# Power.net
KiCad netlist of a schematic drawn in Altium Designer
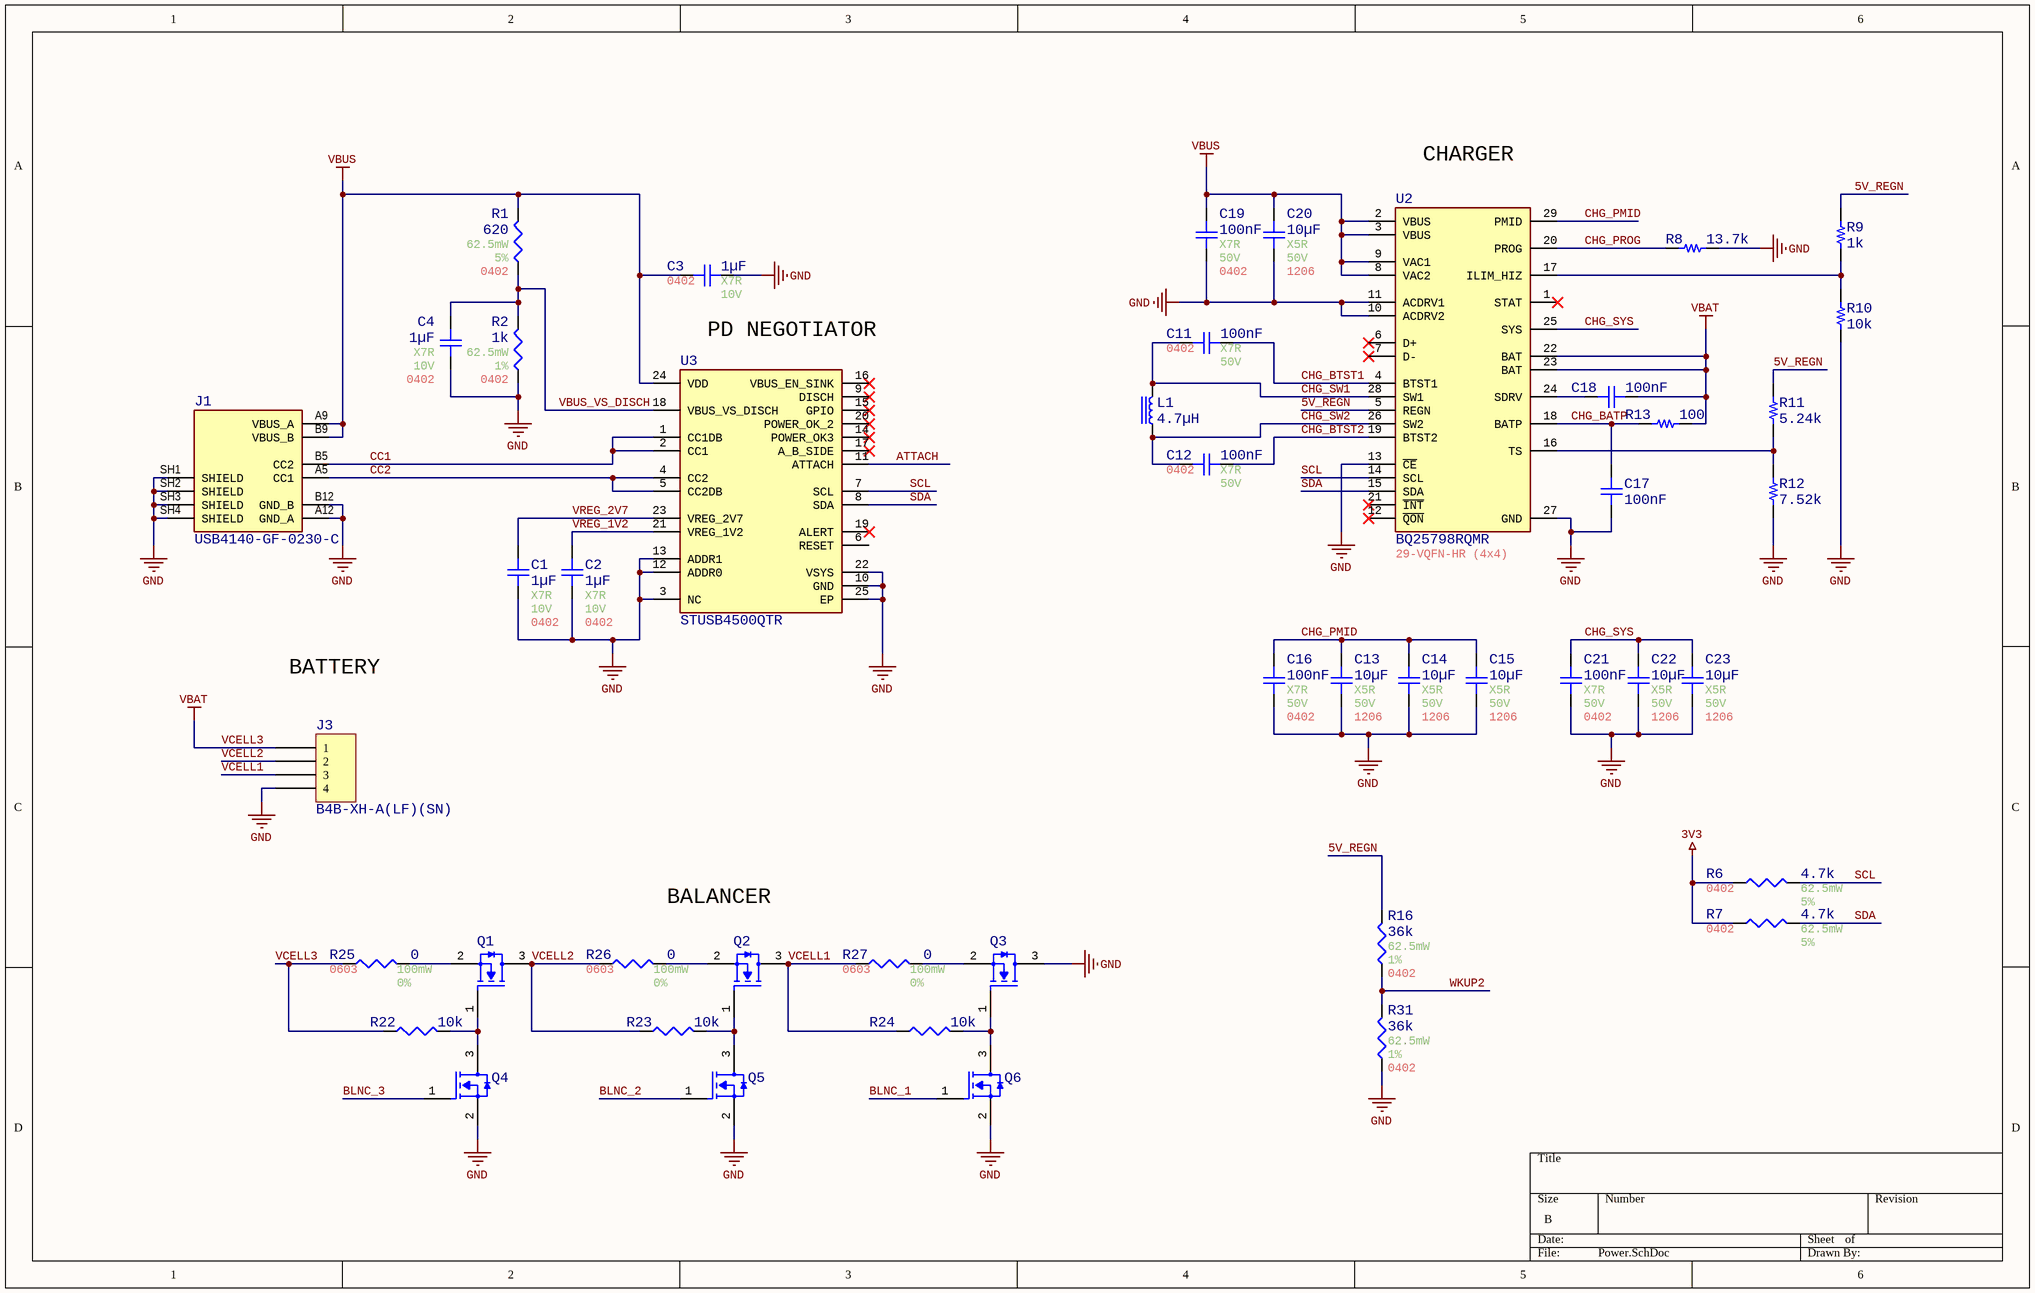
[diagram p0: Power.SchDoc]

(export (version "E")
  (design (tool "Eeschema 10.0.6"))
  (components
    (comp (ref "C1")
      (value "1µF")
      (footprint "Generic 0402 capacitor")
      (description "Cap Cer 1UF 20V X7T 0402")
      (fields
        (field (name "TEMPERATURE COEFFICIENT") "X7R")
        (field (name "VOLTAGE RATING") "10V")
        (field (name "CASE/PACKAGE") "0402")
        (field (name "TOLERANCE") "20%")
        (field (name "Comment") "MAASL105CD7105MFCA01")
      )
      (libsource (lib "Raise Robotics") (part "Unpolarized Capacitor"))
    )
    (comp (ref "C2")
      (value "1µF")
      (footprint "Generic 0402 capacitor")
      (description "Cap Cer 1UF 20V X7T 0402")
      (fields
        (field (name "TEMPERATURE COEFFICIENT") "X7R")
        (field (name "VOLTAGE RATING") "10V")
        (field (name "CASE/PACKAGE") "0402")
        (field (name "TOLERANCE") "20%")
        (field (name "Comment") "MAASL105CD7105MFCA01")
      )
      (libsource (lib "Raise Robotics") (part "Unpolarized Capacitor"))
    )
    (comp (ref "C3")
      (value "1µF")
      (footprint "Generic 0402 capacitor")
      (description "Cap Cer 1UF 20V X7T 0402")
      (fields
        (field (name "TEMPERATURE COEFFICIENT") "X7R")
        (field (name "VOLTAGE RATING") "10V")
        (field (name "CASE/PACKAGE") "0402")
        (field (name "TOLERANCE") "20%")
        (field (name "Comment") "MAASL105CD7105MFCA01")
      )
      (libsource (lib "Raise Robotics") (part "Unpolarized Capacitor"))
    )
    (comp (ref "C4")
      (value "1µF")
      (footprint "Generic 0402 capacitor")
      (description "Cap Cer 1UF 20V X7T 0402")
      (fields
        (field (name "TEMPERATURE COEFFICIENT") "X7R")
        (field (name "VOLTAGE RATING") "10V")
        (field (name "CASE/PACKAGE") "0402")
        (field (name "TOLERANCE") "20%")
        (field (name "Comment") "MAASL105CD7105MFCA01")
      )
      (libsource (lib "Raise Robotics") (part "Unpolarized Capacitor"))
    )
    (comp (ref "C11")
      (value "100nF")
      (footprint "Generic 0402 capacitor")
      (fields
        (field (name "TEMPERATURE COEFFICIENT") "X7R")
        (field (name "VOLTAGE RATING") "50V")
        (field (name "CASE/PACKAGE") "0402")
        (field (name "TOLERANCE") "10%")
        (field (name "Comment") "GRT155R71H104KE01D")
      )
      (libsource (lib "Raise Robotics") (part "Unpolarized Capacitor"))
    )
    (comp (ref "C12")
      (value "100nF")
      (footprint "Generic 0402 capacitor")
      (fields
        (field (name "TEMPERATURE COEFFICIENT") "X7R")
        (field (name "VOLTAGE RATING") "50V")
        (field (name "CASE/PACKAGE") "0402")
        (field (name "TOLERANCE") "10%")
        (field (name "Comment") "GRT155R71H104KE01D")
      )
      (libsource (lib "Raise Robotics") (part "Unpolarized Capacitor"))
    )
    (comp (ref "C13")
      (value "10µF")
      (footprint "Generic 1206 Capacitor")
      (fields
        (field (name "TEMPERATURE COEFFICIENT") "X5R")
        (field (name "VOLTAGE RATING") "50V")
        (field (name "CASE/PACKAGE") "1206")
        (field (name "TOLERANCE") "20%")
        (field (name "Comment") "CL31A106MBHNNNE")
      )
      (libsource (lib "Raise Robotics") (part "Unpolarized Capacitor"))
    )
    (comp (ref "C14")
      (value "10µF")
      (footprint "Generic 1206 Capacitor")
      (fields
        (field (name "TEMPERATURE COEFFICIENT") "X5R")
        (field (name "VOLTAGE RATING") "50V")
        (field (name "CASE/PACKAGE") "1206")
        (field (name "TOLERANCE") "20%")
        (field (name "Comment") "CL31A106MBHNNNE")
      )
      (libsource (lib "Raise Robotics") (part "Unpolarized Capacitor"))
    )
    (comp (ref "C15")
      (value "10µF")
      (footprint "Generic 1206 Capacitor")
      (fields
        (field (name "TEMPERATURE COEFFICIENT") "X5R")
        (field (name "VOLTAGE RATING") "50V")
        (field (name "CASE/PACKAGE") "1206")
        (field (name "TOLERANCE") "20%")
        (field (name "Comment") "CL31A106MBHNNNE")
      )
      (libsource (lib "Raise Robotics") (part "Unpolarized Capacitor"))
    )
    (comp (ref "C16")
      (value "100nF")
      (footprint "Generic 0402 capacitor")
      (fields
        (field (name "TEMPERATURE COEFFICIENT") "X7R")
        (field (name "VOLTAGE RATING") "50V")
        (field (name "CASE/PACKAGE") "0402")
        (field (name "TOLERANCE") "10%")
        (field (name "Comment") "GRT155R71H104KE01D")
      )
      (libsource (lib "Raise Robotics") (part "Unpolarized Capacitor"))
    )
    (comp (ref "C17")
      (value "100nF")
      (footprint "Generic 0402 capacitor")
      (fields (field (name "TOLERANCE") "10%") (field (name "Comment") "GRT155R71H104KE01D"))
      (libsource (lib "Raise Robotics") (part "Unpolarized Capacitor"))
    )
    (comp (ref "C18")
      (value "100nF")
      (footprint "Generic 0402 capacitor")
      (fields (field (name "TOLERANCE") "10%") (field (name "Comment") "GRT155R71H104KE01D"))
      (libsource (lib "Raise Robotics") (part "Unpolarized Capacitor"))
    )
    (comp (ref "C19")
      (value "100nF")
      (footprint "Generic 0402 capacitor")
      (fields
        (field (name "TEMPERATURE COEFFICIENT") "X7R")
        (field (name "VOLTAGE RATING") "50V")
        (field (name "CASE/PACKAGE") "0402")
        (field (name "TOLERANCE") "10%")
        (field (name "Comment") "GRT155R71H104KE01D")
      )
      (libsource (lib "Raise Robotics") (part "Unpolarized Capacitor"))
    )
    (comp (ref "C20")
      (value "10µF")
      (footprint "Generic 1206 Capacitor")
      (fields
        (field (name "TEMPERATURE COEFFICIENT") "X5R")
        (field (name "VOLTAGE RATING") "50V")
        (field (name "CASE/PACKAGE") "1206")
        (field (name "TOLERANCE") "20%")
        (field (name "Comment") "CL31A106MBHNNNE")
      )
      (libsource (lib "Raise Robotics") (part "Unpolarized Capacitor"))
    )
    (comp (ref "C21")
      (value "100nF")
      (footprint "Generic 0402 capacitor")
      (fields
        (field (name "TEMPERATURE COEFFICIENT") "X7R")
        (field (name "VOLTAGE RATING") "50V")
        (field (name "CASE/PACKAGE") "0402")
        (field (name "TOLERANCE") "10%")
        (field (name "Comment") "GRT155R71H104KE01D")
      )
      (libsource (lib "Raise Robotics") (part "Unpolarized Capacitor"))
    )
    (comp (ref "C22")
      (value "10µF")
      (footprint "Generic 1206 Capacitor")
      (fields
        (field (name "TEMPERATURE COEFFICIENT") "X5R")
        (field (name "VOLTAGE RATING") "50V")
        (field (name "CASE/PACKAGE") "1206")
        (field (name "TOLERANCE") "20%")
        (field (name "Comment") "CL31A106MBHNNNE")
      )
      (libsource (lib "Raise Robotics") (part "Unpolarized Capacitor"))
    )
    (comp (ref "C23")
      (value "10µF")
      (footprint "Generic 1206 Capacitor")
      (fields
        (field (name "TEMPERATURE COEFFICIENT") "X5R")
        (field (name "VOLTAGE RATING") "50V")
        (field (name "CASE/PACKAGE") "1206")
        (field (name "TOLERANCE") "20%")
        (field (name "Comment") "CL31A106MBHNNNE")
      )
      (libsource (lib "Raise Robotics") (part "Unpolarized Capacitor"))
    )
    (comp (ref "J1")
      (value "USB4140-GF-0230-C")
      (footprint "USB4140-GF-0230-C")
      (description "USB Connector, 6 Contact(s), Female, Straight, Surface Mount Terminal, Locking, Receptacle")
      (fields (field (name "MANUFACTURER") "Molex"))
      (libsource (lib "Raise Robotics") (part "USB4140-GF-0230-C"))
    )
    (comp (ref "J3")
      (value "B4B-XH-A(LF)(SN)")
      (footprint "JST XH B4B-XH-A")
      (description "CONN HEADER VERT 4POS 2.5MM")
      (fields (field (name "MANUFACTURER") "JST Sales America Inc."))
      (libsource (lib "Celestial Altium Library - altium_library") (part "4 Pin"))
    )
    (comp (ref "L1")
      (value "4.7µH")
      (footprint "IND 1008_2520")
      (description "FIXED IND 4.7UH 1A 110 MOHM SMD")
      (fields (field (name "PART NUMBER") "MLP2520S4R7ST0S1") (field (name "MANUFACTURER") "TDK Corporation"))
      (libsource (lib "Celestial Altium Library - altium_library") (part "Inductor"))
    )
    (comp (ref "Q1")
      (value "DMN61D9UWQ-7")
      (footprint "DMN61D9UWQ-7")
      (description "Small Signal Field-Effect Transistor")
      (libsource (lib "Raise Robotics") (part "n-FET 3 pin SOT"))
    )
    (comp (ref "Q2")
      (value "DMN61D9UWQ-7")
      (footprint "DMN61D9UWQ-7")
      (description "Small Signal Field-Effect Transistor")
      (libsource (lib "Raise Robotics") (part "n-FET 3 pin SOT"))
    )
    (comp (ref "Q3")
      (value "DMN61D9UWQ-7")
      (footprint "DMN61D9UWQ-7")
      (description "Small Signal Field-Effect Transistor")
      (libsource (lib "Raise Robotics") (part "n-FET 3 pin SOT"))
    )
    (comp (ref "Q4")
      (value "DMN61D9UWQ-7")
      (footprint "DMN61D9UWQ-7")
      (description "Small Signal Field-Effect Transistor")
      (libsource (lib "Raise Robotics") (part "n-FET 3 pin SOT"))
    )
    (comp (ref "Q5")
      (value "DMN61D9UWQ-7")
      (footprint "DMN61D9UWQ-7")
      (description "Small Signal Field-Effect Transistor")
      (libsource (lib "Raise Robotics") (part "n-FET 3 pin SOT"))
    )
    (comp (ref "Q6")
      (value "DMN61D9UWQ-7")
      (footprint "DMN61D9UWQ-7")
      (description "Small Signal Field-Effect Transistor")
      (libsource (lib "Raise Robotics") (part "n-FET 3 pin SOT"))
    )
    (comp (ref "R1")
      (value "620")
      (footprint "Generic 0402 Resistor")
      (fields
        (field (name "POWER") "62.5mW")
        (field (name "TOLERANCE") "5%")
        (field (name "CASE/PACKAGE") "0402")
        (field (name "Comment") "RC0402JR-07620RL")
      )
      (libsource (lib "Raise Robotics") (part "Resistor"))
    )
    (comp (ref "R2")
      (value "1k")
      (footprint "Generic 0402 Resistor")
      (fields
        (field (name "POWER") "62.5mW")
        (field (name "TOLERANCE") "1%")
        (field (name "CASE/PACKAGE") "0402")
        (field (name "MANUFACTURER PART NUMBER") "Blank")
        (field (name "Comment") "WR04X1001FTL")
      )
      (libsource (lib "Raise Robotics") (part "Resistor"))
    )
    (comp (ref "R6")
      (value "4.7k")
      (footprint "Generic 0402 Resistor")
      (fields
        (field (name "POWER") "62.5mW")
        (field (name "TOLERANCE") "5%")
        (field (name "CASE/PACKAGE") "0402")
        (field (name "MANUFACTURER PART NUMBER") "Blank")
        (field (name "Comment") "WR04X472JTL")
      )
      (libsource (lib "Raise Robotics") (part "Resistor"))
    )
    (comp (ref "R7")
      (value "4.7k")
      (footprint "Generic 0402 Resistor")
      (fields
        (field (name "POWER") "62.5mW")
        (field (name "TOLERANCE") "5%")
        (field (name "CASE/PACKAGE") "0402")
        (field (name "MANUFACTURER PART NUMBER") "Blank")
        (field (name "Comment") "WR04X472JTL")
      )
      (libsource (lib "Raise Robotics") (part "Resistor"))
    )
    (comp (ref "R8")
      (value "13.7k")
      (footprint "RES_0402")
      (description "RES 0402")
      (libsource (lib "IC") (part "RES_0402"))
    )
    (comp (ref "R9")
      (value "1k")
      (footprint "RES_0402")
      (description "RES 0402")
      (libsource (lib "IC") (part "RES_0402"))
    )
    (comp (ref "R10")
      (value "10k")
      (footprint "RES_0402")
      (description "RES 0402")
      (libsource (lib "IC") (part "RES_0402"))
    )
    (comp (ref "R11")
      (value "5.24k")
      (footprint "RES_0402")
      (description "RES 0402")
      (libsource (lib "IC") (part "RES_0402"))
    )
    (comp (ref "R12")
      (value "7.52k")
      (footprint "RES_0402")
      (description "RES 0402")
      (libsource (lib "IC") (part "RES_0402"))
    )
    (comp (ref "R13")
      (value "100")
      (footprint "RES_0402")
      (description "RES 0402")
      (libsource (lib "IC") (part "RES_0402"))
    )
    (comp (ref "R16")
      (value "36k")
      (footprint "Generic 0402 Resistor")
      (fields
        (field (name "POWER") "62.5mW")
        (field (name "TOLERANCE") "1%")
        (field (name "CASE/PACKAGE") "0402")
        (field (name "Comment") "AC0402FR-0736KL")
      )
      (libsource (lib "Raise Robotics") (part "Resistor"))
    )
    (comp (ref "R22")
      (value "10k")
      (footprint "Generic 0402 Resistor")
      (fields
        (field (name "POWER") "62.5mW")
        (field (name "TOLERANCE") "5%")
        (field (name "MANUFACTURER PART NUMBER") "Blank")
      )
      (libsource (lib "Raise Robotics") (part "Resistor"))
    )
    (comp (ref "R23")
      (value "10k")
      (footprint "Generic 0402 Resistor")
      (fields
        (field (name "POWER") "62.5mW")
        (field (name "TOLERANCE") "5%")
        (field (name "MANUFACTURER PART NUMBER") "Blank")
      )
      (libsource (lib "Raise Robotics") (part "Resistor"))
    )
    (comp (ref "R24")
      (value "10k")
      (footprint "Generic 0402 Resistor")
      (fields
        (field (name "POWER") "62.5mW")
        (field (name "TOLERANCE") "5%")
        (field (name "MANUFACTURER PART NUMBER") "Blank")
      )
      (libsource (lib "Raise Robotics") (part "Resistor"))
    )
    (comp (ref "R25")
      (value "0")
      (footprint "Generic 0603 Resistor")
      (description "Fixed Resistor, Metal Glaze/thick Film, 0.1W, 0ohm, Surface Mount, 0603")
      (fields
        (field (name "POWER") "100mW")
        (field (name "TOLERANCE") "0%")
        (field (name "CASE/PACKAGE") "0603")
        (field (name "MANUFACTURER PART NUMBER") "Blank")
        (field (name "Comment") "WR06X000PTL")
      )
      (libsource (lib "Raise Robotics") (part "Resistor"))
    )
    (comp (ref "R26")
      (value "0")
      (footprint "Generic 0603 Resistor")
      (description "Fixed Resistor, Metal Glaze/thick Film, 0.1W, 0ohm, Surface Mount, 0603")
      (fields
        (field (name "POWER") "100mW")
        (field (name "TOLERANCE") "0%")
        (field (name "CASE/PACKAGE") "0603")
        (field (name "MANUFACTURER PART NUMBER") "Blank")
        (field (name "Comment") "WR06X000PTL")
      )
      (libsource (lib "Raise Robotics") (part "Resistor"))
    )
    (comp (ref "R27")
      (value "0")
      (footprint "Generic 0603 Resistor")
      (description "Fixed Resistor, Metal Glaze/thick Film, 0.1W, 0ohm, Surface Mount, 0603")
      (fields
        (field (name "POWER") "100mW")
        (field (name "TOLERANCE") "0%")
        (field (name "CASE/PACKAGE") "0603")
        (field (name "MANUFACTURER PART NUMBER") "Blank")
        (field (name "Comment") "WR06X000PTL")
      )
      (libsource (lib "Raise Robotics") (part "Resistor"))
    )
    (comp (ref "R31")
      (value "36k")
      (footprint "Generic 0402 Resistor")
      (fields
        (field (name "POWER") "62.5mW")
        (field (name "TOLERANCE") "1%")
        (field (name "CASE/PACKAGE") "0402")
        (field (name "Comment") "AC0402FR-0736KL")
      )
      (libsource (lib "Raise Robotics") (part "Resistor"))
    )
    (comp (ref "U2")
      (value "BQ25798RQMR")
      (footprint "29-VQFN-HR (4x4)")
      (fields (field (name "CASE/PACKAGE") "29-VQFN-HR (4x4)"))
      (libsource (lib "Raise Robotics") (part "BQ25798"))
    )
    (comp (ref "U3")
      (value "STUSB4500QTR")
      (footprint "FP-QFN-24-EP_4x4-MFG")
      (description "Super Speed USB Controller USB 1.2/USB 2.0 5V/9V/12V/15V/18V T/R 24-Pin QFN EP")
      (libsource (lib "Raise Robotics") (part "STUSB4500QTR"))
    )
  )
  (nets
    (net (code "1") (name "/5V_REGN") (class "Default")
      (node (ref "R11") (pin "1") (pinfunction "1_1") (pintype "passive"))
      (node (ref "R16") (pin "2") (pinfunction "2_2") (pintype "passive"))
      (node (ref "R9") (pin "1") (pinfunction "1_1") (pintype "passive"))
      (node (ref "U2") (pin "5") (pinfunction "REGN_5") (pintype "passive"))
    )
    (net (code "2") (name "/ATTACH") (class "Default")
      (node (ref "U3") (pin "11") (pinfunction "ATTACH_11") (pintype "passive"))
    )
    (net (code "3") (name "/BLNC_1") (class "Default")
      (node (ref "Q6") (pin "1") (pinfunction "GATE_1") (pintype "passive"))
    )
    (net (code "4") (name "/BLNC_2") (class "Default")
      (node (ref "Q5") (pin "1") (pinfunction "GATE_1") (pintype "passive"))
    )
    (net (code "5") (name "/BLNC_3") (class "Default")
      (node (ref "Q4") (pin "1") (pinfunction "GATE_1") (pintype "passive"))
    )
    (net (code "6") (name "/CC1") (class "Default")
      (node (ref "J1") (pin "B5") (pinfunction "CC2_B5") (pintype "passive"))
      (node (ref "U3") (pin "1") (pinfunction "CC1DB_1") (pintype "passive"))
      (node (ref "U3") (pin "2") (pinfunction "CC1_2") (pintype "passive"))
    )
    (net (code "7") (name "/CC2") (class "Default")
      (node (ref "J1") (pin "A5") (pinfunction "CC1_A5") (pintype "passive"))
      (node (ref "U3") (pin "4") (pinfunction "CC2_4") (pintype "passive"))
      (node (ref "U3") (pin "5") (pinfunction "CC2DB_5") (pintype "passive"))
    )
    (net (code "8") (name "/CHG_BATP") (class "Default")
      (node (ref "C17") (pin "1") (pinfunction "1_1") (pintype "passive"))
      (node (ref "R13") (pin "2") (pinfunction "2_2") (pintype "passive"))
      (node (ref "U2") (pin "18") (pinfunction "BATP_18") (pintype "passive"))
    )
    (net (code "9") (name "/CHG_BTST1") (class "Default")
      (node (ref "C11") (pin "1") (pinfunction "1_1") (pintype "passive"))
      (node (ref "U2") (pin "4") (pinfunction "BTST1_4") (pintype "passive"))
    )
    (net (code "10") (name "/CHG_BTST2") (class "Default")
      (node (ref "C12") (pin "1") (pinfunction "1_1") (pintype "passive"))
      (node (ref "U2") (pin "19") (pinfunction "BTST2_19") (pintype "passive"))
    )
    (net (code "11") (name "/CHG_PMID") (class "Default")
      (node (ref "C13") (pin "2") (pinfunction "2_2") (pintype "passive"))
      (node (ref "C14") (pin "2") (pinfunction "2_2") (pintype "passive"))
      (node (ref "C15") (pin "2") (pinfunction "2_2") (pintype "passive"))
      (node (ref "C16") (pin "1") (pinfunction "1_1") (pintype "passive"))
      (node (ref "U2") (pin "29") (pinfunction "PMID_29") (pintype "passive"))
    )
    (net (code "12") (name "/CHG_PROG") (class "Default")
      (node (ref "R8") (pin "2") (pinfunction "2_2") (pintype "passive"))
      (node (ref "U2") (pin "20") (pinfunction "PROG_20") (pintype "passive"))
    )
    (net (code "13") (name "/CHG_SW1") (class "Default")
      (node (ref "C11") (pin "2") (pinfunction "2_2") (pintype "passive"))
      (node (ref "L1") (pin "2") (pinfunction "2_2") (pintype "passive"))
      (node (ref "U2") (pin "28") (pinfunction "SW1_28") (pintype "passive"))
    )
    (net (code "14") (name "/CHG_SW2") (class "Default")
      (node (ref "C12") (pin "2") (pinfunction "2_2") (pintype "passive"))
      (node (ref "L1") (pin "1") (pinfunction "1_1") (pintype "passive"))
      (node (ref "U2") (pin "26") (pinfunction "SW2_26") (pintype "passive"))
    )
    (net (code "15") (name "/CHG_SYS") (class "Default")
      (node (ref "C21") (pin "1") (pinfunction "1_1") (pintype "passive"))
      (node (ref "C22") (pin "2") (pinfunction "2_2") (pintype "passive"))
      (node (ref "C23") (pin "2") (pinfunction "2_2") (pintype "passive"))
      (node (ref "U2") (pin "25") (pinfunction "SYS_25") (pintype "passive"))
    )
    (net (code "16") (name "/SCL") (class "Default")
      (node (ref "R6") (pin "2") (pinfunction "2_2") (pintype "passive"))
      (node (ref "U2") (pin "14") (pinfunction "SCL_14") (pintype "passive"))
      (node (ref "U3") (pin "7") (pinfunction "SCL_7") (pintype "passive"))
    )
    (net (code "17") (name "/SDA") (class "Default")
      (node (ref "R7") (pin "2") (pinfunction "2_2") (pintype "passive"))
      (node (ref "U2") (pin "15") (pinfunction "SDA_15") (pintype "passive"))
      (node (ref "U3") (pin "8") (pinfunction "SDA_8") (pintype "passive"))
    )
    (net (code "18") (name "/VBUS_VS_DISCH") (class "Default")
      (node (ref "C4") (pin "2") (pinfunction "2_2") (pintype "passive"))
      (node (ref "R1") (pin "1") (pinfunction "1_1") (pintype "passive"))
      (node (ref "R2") (pin "2") (pinfunction "2_2") (pintype "passive"))
      (node (ref "U3") (pin "18") (pinfunction "VBUS_VS_DISCH_18") (pintype "passive"))
    )
    (net (code "19") (name "/VCELL1") (class "Default")
      (node (ref "J3") (pin "3") (pinfunction "3_3") (pintype "passive"))
      (node (ref "Q2") (pin "3") (pinfunction "DRAIN_3") (pintype "passive"))
      (node (ref "R24") (pin "1") (pinfunction "1_1") (pintype "passive"))
      (node (ref "R27") (pin "1") (pinfunction "1_1") (pintype "passive"))
    )
    (net (code "20") (name "/VCELL2") (class "Default")
      (node (ref "J3") (pin "2") (pinfunction "2_2") (pintype "passive"))
      (node (ref "Q1") (pin "3") (pinfunction "DRAIN_3") (pintype "passive"))
      (node (ref "R23") (pin "1") (pinfunction "1_1") (pintype "passive"))
      (node (ref "R26") (pin "1") (pinfunction "1_1") (pintype "passive"))
    )
    (net (code "21") (name "/VREG_1V2") (class "Default")
      (node (ref "C2") (pin "2") (pinfunction "2_2") (pintype "passive"))
      (node (ref "U3") (pin "21") (pinfunction "VREG_1V2_21") (pintype "passive"))
    )
    (net (code "22") (name "/VREG_2V7") (class "Default")
      (node (ref "C1") (pin "2") (pinfunction "2_2") (pintype "passive"))
      (node (ref "U3") (pin "23") (pinfunction "VREG_2V7_23") (pintype "passive"))
    )
    (net (code "23") (name "/WKUP2") (class "Default")
      (node (ref "R16") (pin "1") (pinfunction "1_1") (pintype "passive"))
      (node (ref "R31") (pin "2") (pinfunction "2_2") (pintype "passive"))
    )
    (net (code "24") (name "3V3") (class "Default")
      (node (ref "R6") (pin "1") (pinfunction "1_1") (pintype "passive"))
      (node (ref "R7") (pin "1") (pinfunction "1_1") (pintype "passive"))
    )
    (net (code "25") (name "GND") (class "Default")
      (node (ref "C1") (pin "1") (pinfunction "1_1") (pintype "passive"))
      (node (ref "C13") (pin "1") (pinfunction "1_1") (pintype "passive"))
      (node (ref "C14") (pin "1") (pinfunction "1_1") (pintype "passive"))
      (node (ref "C15") (pin "1") (pinfunction "1_1") (pintype "passive"))
      (node (ref "C16") (pin "2") (pinfunction "2_2") (pintype "passive"))
      (node (ref "C17") (pin "2") (pinfunction "2_2") (pintype "passive"))
      (node (ref "C19") (pin "2") (pinfunction "2_2") (pintype "passive"))
      (node (ref "C2") (pin "1") (pinfunction "1_1") (pintype "passive"))
      (node (ref "C20") (pin "1") (pinfunction "1_1") (pintype "passive"))
      (node (ref "C21") (pin "2") (pinfunction "2_2") (pintype "passive"))
      (node (ref "C22") (pin "1") (pinfunction "1_1") (pintype "passive"))
      (node (ref "C23") (pin "1") (pinfunction "1_1") (pintype "passive"))
      (node (ref "C3") (pin "1") (pinfunction "1_1") (pintype "passive"))
      (node (ref "C4") (pin "1") (pinfunction "1_1") (pintype "passive"))
      (node (ref "J1") (pin "A12") (pinfunction "GND_A_A12") (pintype "passive"))
      (node (ref "J1") (pin "B12") (pinfunction "GND_B_B12") (pintype "passive"))
      (node (ref "J1") (pin "SH1") (pinfunction "SHIELD_SH1") (pintype "passive"))
      (node (ref "J1") (pin "SH2") (pinfunction "SHIELD_SH2") (pintype "passive"))
      (node (ref "J1") (pin "SH3") (pinfunction "SHIELD_SH3") (pintype "passive"))
      (node (ref "J1") (pin "SH4") (pinfunction "SHIELD_SH4") (pintype "passive"))
      (node (ref "J3") (pin "4") (pinfunction "4_4") (pintype "passive"))
      (node (ref "Q3") (pin "3") (pinfunction "DRAIN_3") (pintype "passive"))
      (node (ref "Q4") (pin "2") (pinfunction "SOURCE_2") (pintype "passive"))
      (node (ref "Q5") (pin "2") (pinfunction "SOURCE_2") (pintype "passive"))
      (node (ref "Q6") (pin "2") (pinfunction "SOURCE_2") (pintype "passive"))
      (node (ref "R10") (pin "2") (pinfunction "2_2") (pintype "passive"))
      (node (ref "R12") (pin "2") (pinfunction "2_2") (pintype "passive"))
      (node (ref "R2") (pin "1") (pinfunction "1_1") (pintype "passive"))
      (node (ref "R31") (pin "1") (pinfunction "1_1") (pintype "passive"))
      (node (ref "R8") (pin "1") (pinfunction "1_1") (pintype "passive"))
      (node (ref "U2") (pin "10") (pinfunction "ACDRV2_10") (pintype "passive"))
      (node (ref "U2") (pin "11") (pinfunction "ACDRV1_11") (pintype "passive"))
      (node (ref "U2") (pin "13") (pinfunction "~{CE}_13") (pintype "passive"))
      (node (ref "U2") (pin "27") (pinfunction "GND_27") (pintype "passive"))
      (node (ref "U3") (pin "10") (pinfunction "GND_10") (pintype "passive"))
      (node (ref "U3") (pin "12") (pinfunction "ADDR0_12") (pintype "passive"))
      (node (ref "U3") (pin "13") (pinfunction "ADDR1_13") (pintype "passive"))
      (node (ref "U3") (pin "22") (pinfunction "VSYS_22") (pintype "passive"))
      (node (ref "U3") (pin "25") (pinfunction "EP_25") (pintype "passive"))
      (node (ref "U3") (pin "3") (pinfunction "NC_3") (pintype "passive"))
    )
    (net (code "26") (name "Net-(Q1-GATE)") (class "Default")
      (node (ref "Q1") (pin "1") (pinfunction "GATE_1") (pintype "passive"))
      (node (ref "Q4") (pin "3") (pinfunction "DRAIN_3") (pintype "passive"))
      (node (ref "R22") (pin "2") (pinfunction "2_2") (pintype "passive"))
    )
    (net (code "27") (name "Net-(Q1-SOURCE)") (class "Default")
      (node (ref "Q1") (pin "2") (pinfunction "SOURCE_2") (pintype "passive"))
      (node (ref "R25") (pin "2") (pinfunction "2_2") (pintype "passive"))
    )
    (net (code "28") (name "Net-(Q2-GATE)") (class "Default")
      (node (ref "Q2") (pin "1") (pinfunction "GATE_1") (pintype "passive"))
      (node (ref "Q5") (pin "3") (pinfunction "DRAIN_3") (pintype "passive"))
      (node (ref "R23") (pin "2") (pinfunction "2_2") (pintype "passive"))
    )
    (net (code "29") (name "Net-(Q2-SOURCE)") (class "Default")
      (node (ref "Q2") (pin "2") (pinfunction "SOURCE_2") (pintype "passive"))
      (node (ref "R26") (pin "2") (pinfunction "2_2") (pintype "passive"))
    )
    (net (code "30") (name "Net-(Q3-GATE)") (class "Default")
      (node (ref "Q3") (pin "1") (pinfunction "GATE_1") (pintype "passive"))
      (node (ref "Q6") (pin "3") (pinfunction "DRAIN_3") (pintype "passive"))
      (node (ref "R24") (pin "2") (pinfunction "2_2") (pintype "passive"))
    )
    (net (code "31") (name "Net-(Q3-SOURCE)") (class "Default")
      (node (ref "Q3") (pin "2") (pinfunction "SOURCE_2") (pintype "passive"))
      (node (ref "R27") (pin "2") (pinfunction "2_2") (pintype "passive"))
    )
    (net (code "32") (name "Net-(U2-ILIM_HIZ)") (class "Default")
      (node (ref "R10") (pin "1") (pinfunction "1_1") (pintype "passive"))
      (node (ref "R9") (pin "2") (pinfunction "2_2") (pintype "passive"))
      (node (ref "U2") (pin "17") (pinfunction "ILIM_HIZ_17") (pintype "passive"))
    )
    (net (code "33") (name "Net-(U2-SDRV)") (class "Default")
      (node (ref "C18") (pin "1") (pinfunction "1_1") (pintype "passive"))
      (node (ref "U2") (pin "24") (pinfunction "SDRV_24") (pintype "passive"))
    )
    (net (code "34") (name "Net-(U2-TS)") (class "Default")
      (node (ref "R11") (pin "2") (pinfunction "2_2") (pintype "passive"))
      (node (ref "R12") (pin "1") (pinfunction "1_1") (pintype "passive"))
      (node (ref "U2") (pin "16") (pinfunction "TS_16") (pintype "passive"))
    )
    (net (code "35") (name "VBAT") (class "Default")
      (node (ref "C18") (pin "2") (pinfunction "2_2") (pintype "passive"))
      (node (ref "J3") (pin "1") (pinfunction "1_1") (pintype "passive"))
      (node (ref "R13") (pin "1") (pinfunction "1_1") (pintype "passive"))
      (node (ref "R22") (pin "1") (pinfunction "1_1") (pintype "passive"))
      (node (ref "R25") (pin "1") (pinfunction "1_1") (pintype "passive"))
      (node (ref "U2") (pin "22") (pinfunction "BAT_22") (pintype "passive"))
      (node (ref "U2") (pin "23") (pinfunction "BAT_23") (pintype "passive"))
    )
    (net (code "36") (name "VBUS") (class "Default")
      (node (ref "C19") (pin "1") (pinfunction "1_1") (pintype "passive"))
      (node (ref "C20") (pin "2") (pinfunction "2_2") (pintype "passive"))
      (node (ref "C3") (pin "2") (pinfunction "2_2") (pintype "passive"))
      (node (ref "J1") (pin "A9") (pinfunction "VBUS_A_A9") (pintype "passive"))
      (node (ref "J1") (pin "B9") (pinfunction "VBUS_B_B9") (pintype "passive"))
      (node (ref "R1") (pin "2") (pinfunction "2_2") (pintype "passive"))
      (node (ref "U2") (pin "2") (pinfunction "VBUS_2") (pintype "passive"))
      (node (ref "U2") (pin "3") (pinfunction "VBUS_3") (pintype "passive"))
      (node (ref "U2") (pin "8") (pinfunction "VAC2_8") (pintype "passive"))
      (node (ref "U2") (pin "9") (pinfunction "VAC1_9") (pintype "passive"))
      (node (ref "U3") (pin "24") (pinfunction "VDD_24") (pintype "passive"))
    )
    (net (code "37") (name "unconnected-(U2-D+-Pad6)") (class "Default")
      (node (ref "U2") (pin "6") (pinfunction "D+_6") (pintype "passive+no_connect"))
    )
    (net (code "38") (name "unconnected-(U2-D--Pad7)") (class "Default")
      (node (ref "U2") (pin "7") (pinfunction "D-_7") (pintype "passive+no_connect"))
    )
    (net (code "39") (name "unconnected-(U2-STAT-Pad1)") (class "Default")
      (node (ref "U2") (pin "1") (pinfunction "STAT_1") (pintype "passive+no_connect"))
    )
    (net (code "40") (name "unconnected-(U2-~{INT}-Pad21)") (class "Default")
      (node (ref "U2") (pin "21") (pinfunction "~{INT}_21") (pintype "passive+no_connect"))
    )
    (net (code "41") (name "unconnected-(U2-~{QON}-Pad12)") (class "Default")
      (node (ref "U2") (pin "12") (pinfunction "~{QON}_12") (pintype "passive+no_connect"))
    )
    (net (code "42") (name "unconnected-(U3-ALERT-Pad19)") (class "Default")
      (node (ref "U3") (pin "19") (pinfunction "ALERT_19") (pintype "passive+no_connect"))
    )
    (net (code "43") (name "unconnected-(U3-A_B_SIDE-Pad17)") (class "Default")
      (node (ref "U3") (pin "17") (pinfunction "A_B_SIDE_17") (pintype "passive+no_connect"))
    )
    (net (code "44") (name "unconnected-(U3-DISCH-Pad9)") (class "Default")
      (node (ref "U3") (pin "9") (pinfunction "DISCH_9") (pintype "passive+no_connect"))
    )
    (net (code "45") (name "unconnected-(U3-GPIO-Pad15)") (class "Default")
      (node (ref "U3") (pin "15") (pinfunction "GPIO_15") (pintype "passive+no_connect"))
    )
    (net (code "46") (name "unconnected-(U3-POWER_OK3-Pad14)") (class "Default")
      (node (ref "U3") (pin "14") (pinfunction "POWER_OK3_14") (pintype "passive+no_connect"))
    )
    (net (code "47") (name "unconnected-(U3-POWER_OK_2-Pad20)") (class "Default")
      (node (ref "U3") (pin "20") (pinfunction "POWER_OK_2_20") (pintype "passive+no_connect"))
    )
    (net (code "48") (name "unconnected-(U3-RESET-Pad6)") (class "Default")
      (node (ref "U3") (pin "6") (pinfunction "RESET_6") (pintype "passive"))
    )
    (net (code "49") (name "unconnected-(U3-VBUS_EN_SINK-Pad16)") (class "Default")
      (node (ref "U3") (pin "16") (pinfunction "VBUS_EN_SINK_16") (pintype "passive+no_connect"))
    )
  )
)
